# SID-Monitor.net
KiCad netlist of a schematic drawn in EAGLE
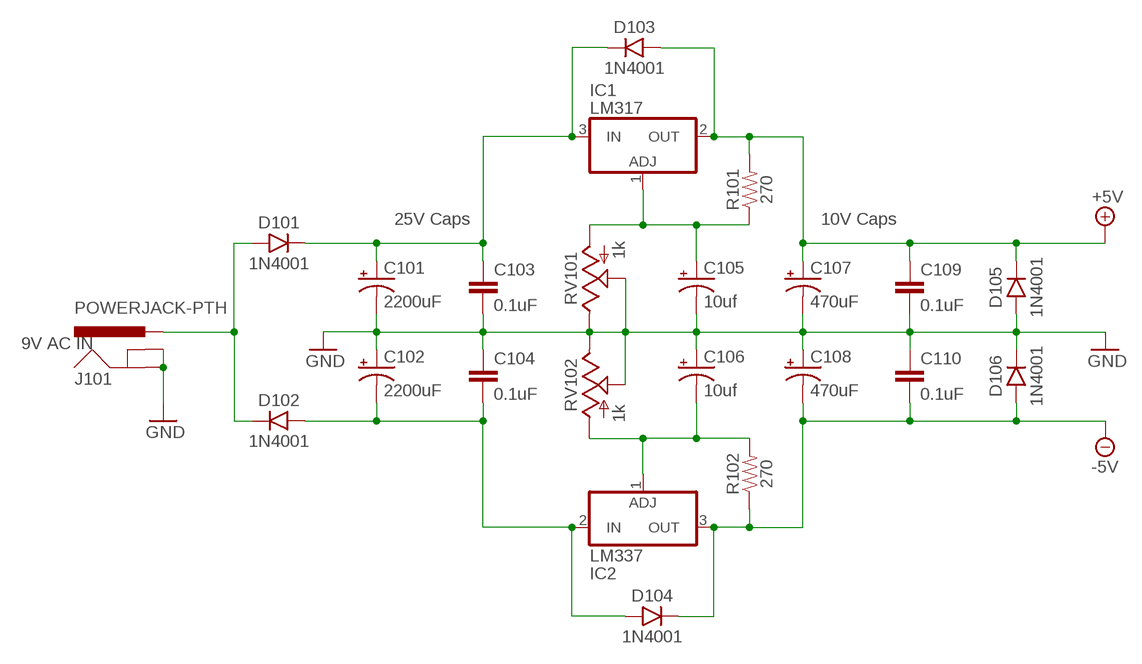
[diagram p0: schematic, sheet 1]
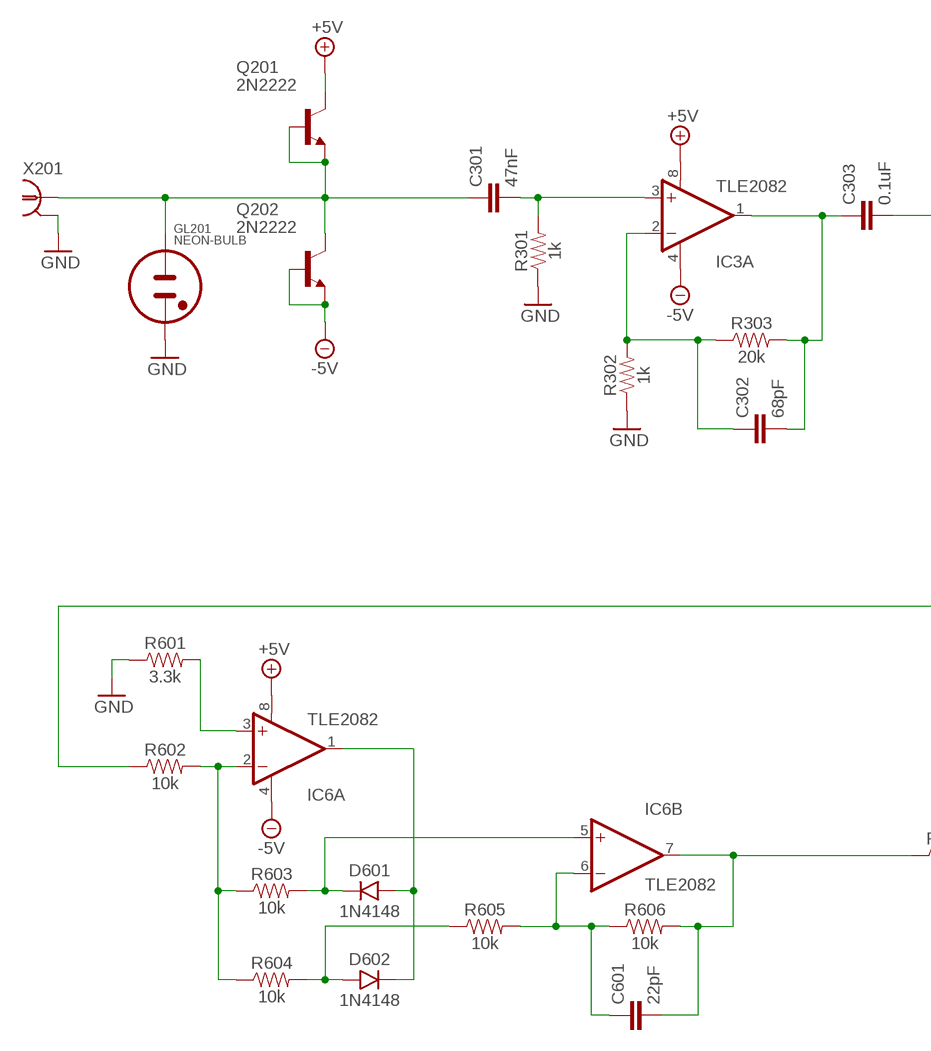
[diagram p1: schematic, sheet 2, part 1 of 2]
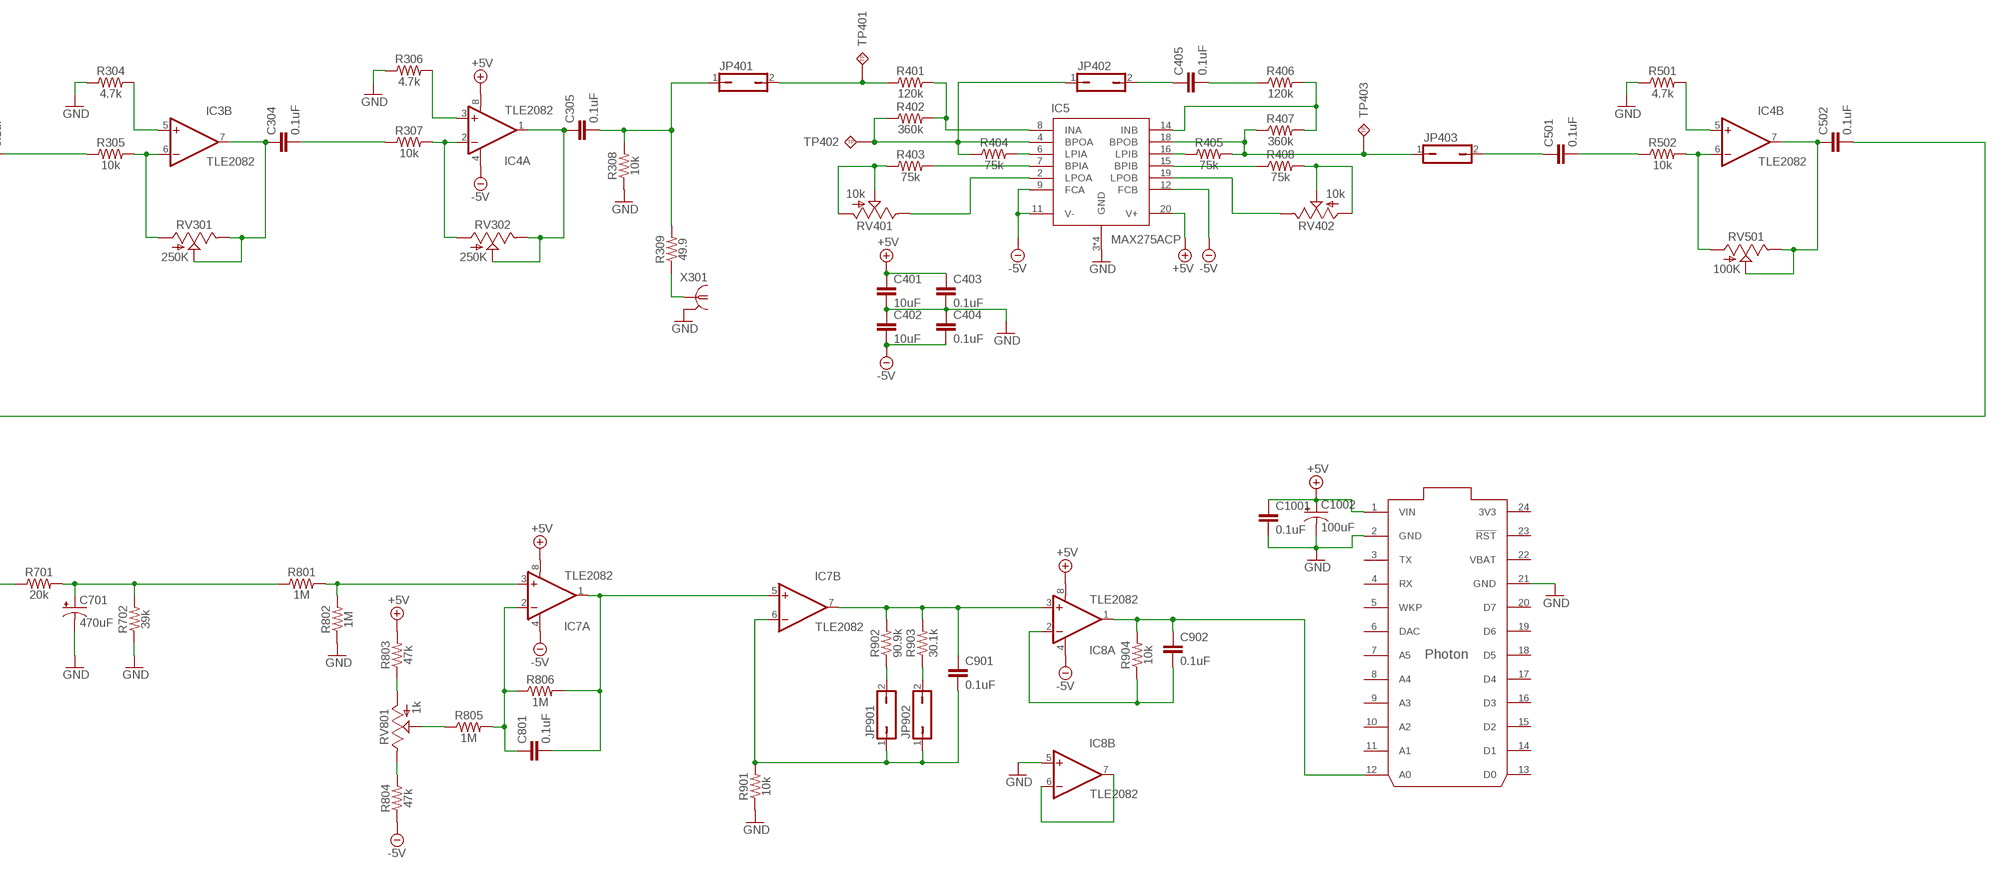
[diagram p2: schematic, sheet 2, part 2 of 2]

(export (version "E")
  (design (tool "Eeschema 10.0.6"))
  (components
    (comp (ref "C301")
      (value "47nF")
      (footprint "eagle-import:CAPACITOR-2.5MM")
      (libsource (lib "eagle-import") (part "CAPACITOR-2.5MM"))
    )
    (comp (ref "C302")
      (value "68pF")
      (footprint "eagle-import:CAPACITOR-2.5MM")
      (libsource (lib "eagle-import") (part "CAPACITOR-2.5MM"))
    )
    (comp (ref "C303")
      (value "0.1uF")
      (footprint "eagle-import:CAPACITOR-2.5MM")
      (libsource (lib "eagle-import") (part "CAPACITOR-2.5MM"))
    )
    (comp (ref "C304")
      (value "0.1uF")
      (footprint "eagle-import:CAPACITOR-2.5MM")
      (libsource (lib "eagle-import") (part "CAPACITOR-2.5MM"))
    )
    (comp (ref "C305")
      (value "0.1uF")
      (footprint "eagle-import:CAPACITOR-2.5MM")
      (libsource (lib "eagle-import") (part "CAPACITOR-2.5MM"))
    )
    (comp (ref "C401")
      (value "10uF")
      (footprint "eagle-import:CAPACITOR-5MM")
      (libsource (lib "eagle-import") (part "CAPACITOR-5MM"))
    )
    (comp (ref "C402")
      (value "10uF")
      (footprint "eagle-import:CAPACITOR-5MM")
      (libsource (lib "eagle-import") (part "CAPACITOR-5MM"))
    )
    (comp (ref "C403")
      (value "0.1uF")
      (footprint "eagle-import:CAPACITOR-2.5MM")
      (libsource (lib "eagle-import") (part "CAPACITOR-2.5MM"))
    )
    (comp (ref "C404")
      (value "0.1uF")
      (footprint "eagle-import:CAPACITOR-2.5MM")
      (libsource (lib "eagle-import") (part "CAPACITOR-2.5MM"))
    )
    (comp (ref "C405")
      (value "0.1uF")
      (footprint "eagle-import:CAPACITOR-2.5MM")
      (libsource (lib "eagle-import") (part "CAPACITOR-2.5MM"))
    )
    (comp (ref "C501")
      (value "0.1uF")
      (footprint "eagle-import:CAPACITOR-2.5MM")
      (libsource (lib "eagle-import") (part "CAPACITOR-2.5MM"))
    )
    (comp (ref "C502")
      (value "0.1uF")
      (footprint "eagle-import:CAPACITOR-2.5MM")
      (libsource (lib "eagle-import") (part "CAPACITOR-2.5MM"))
    )
    (comp (ref "C601")
      (value "22pF")
      (footprint "eagle-import:CAPACITOR-2.5MM")
      (libsource (lib "eagle-import") (part "CAPACITOR-2.5MM"))
    )
    (comp (ref "C701")
      (value "470uF")
      (footprint "eagle-import:CAP-POL-3.5-8")
      (libsource (lib "eagle-import") (part "CAPACITOR-POLARIZED-3.5-8"))
    )
    (comp (ref "C801")
      (value "0.1uF")
      (footprint "eagle-import:CAPACITOR-2.5MM")
      (libsource (lib "eagle-import") (part "CAPACITOR-2.5MM"))
    )
    (comp (ref "C901")
      (value "0.1uF")
      (footprint "eagle-import:CAPACITOR-2.5MM")
      (libsource (lib "eagle-import") (part "CAPACITOR-2.5MM"))
    )
    (comp (ref "C902")
      (value "0.1uF")
      (footprint "eagle-import:CAPACITOR-2.5MM")
      (libsource (lib "eagle-import") (part "CAPACITOR-2.5MM"))
    )
    (comp (ref "C1001")
      (value "0.1uF")
      (footprint "eagle-import:CAPACITOR-2.5MM")
      (libsource (lib "eagle-import") (part "CAPACITOR-2.5MM"))
    )
    (comp (ref "C1002")
      (value "100uF")
      (footprint "eagle-import:CAP-POL-3.5-8")
      (libsource (lib "eagle-import") (part "CAPACITOR-POLARIZED-3.5-8"))
    )
    (comp (ref "D601")
      (value "1N4148")
      (footprint "eagle-import:DIODE-DO-35")
      (libsource (lib "eagle-import") (part "DIODE-1N4148"))
    )
    (comp (ref "D602")
      (value "1N4148")
      (footprint "eagle-import:DIODE-DO-35")
      (libsource (lib "eagle-import") (part "DIODE-1N4148"))
    )
    (comp (ref "GL201")
      (value "NEON-BULB")
      (footprint "eagle-import:NEON-BULB")
      (libsource (lib "eagle-import") (part "NEON-BULB"))
    )
    (comp (ref "IC3")
      (value "TLE2082")
      (footprint "eagle-import:DIP08")
      (libsource (lib "eagle-import") (part "TLE2082"))
    )
    (comp (ref "IC4")
      (value "TLE2082")
      (footprint "eagle-import:DIP08")
      (libsource (lib "eagle-import") (part "TLE2082"))
    )
    (comp (ref "IC5")
      (value "MAX275ACP")
      (footprint "eagle-import:DIP20")
      (libsource (lib "eagle-import") (part "MAX275ACP"))
    )
    (comp (ref "IC6")
      (value "TLE2082")
      (footprint "eagle-import:DIP08")
      (libsource (lib "eagle-import") (part "TLE2082"))
    )
    (comp (ref "IC7")
      (value "TLE2082")
      (footprint "eagle-import:DIP08")
      (libsource (lib "eagle-import") (part "TLE2082"))
    )
    (comp (ref "IC8")
      (value "TLE2082")
      (footprint "eagle-import:DIP08")
      (libsource (lib "eagle-import") (part "TLE2082"))
    )
    (comp (ref "IC9")
      (value "PHOTON")
      (footprint "eagle-import:PHOTON")
      (libsource (lib "eagle-import") (part "PHOTON_WITH_HEADERS"))
    )
    (comp (ref "JP401")
      (value "JUMPER1")
      (footprint "eagle-import:JUMPER1")
      (libsource (lib "eagle-import") (part "JUMPER1"))
    )
    (comp (ref "JP402")
      (value "JUMPER1")
      (footprint "eagle-import:JUMPER1")
      (libsource (lib "eagle-import") (part "JUMPER1"))
    )
    (comp (ref "JP403")
      (value "JUMPER1")
      (footprint "eagle-import:JUMPER1")
      (libsource (lib "eagle-import") (part "JUMPER1"))
    )
    (comp (ref "JP901")
      (value "JUMPER1")
      (footprint "eagle-import:JUMPER1")
      (libsource (lib "eagle-import") (part "JUMPER1"))
    )
    (comp (ref "JP902")
      (value "JUMPER1")
      (footprint "eagle-import:JUMPER1")
      (libsource (lib "eagle-import") (part "JUMPER1"))
    )
    (comp (ref "Q201")
      (value "2N2222")
      (footprint "eagle-import:TO92-INLINE")
      (libsource (lib "eagle-import") (part "2N2222"))
    )
    (comp (ref "Q202")
      (value "2N2222")
      (footprint "eagle-import:TO92-INLINE")
      (libsource (lib "eagle-import") (part "2N2222"))
    )
    (comp (ref "R301")
      (value "1k")
      (footprint "eagle-import:AXIAL-7.5MM")
      (libsource (lib "eagle-import") (part "RESISTOR-7.5MM"))
    )
    (comp (ref "R302")
      (value "1k")
      (footprint "eagle-import:AXIAL-7.5MM")
      (libsource (lib "eagle-import") (part "RESISTOR-7.5MM"))
    )
    (comp (ref "R303")
      (value "20k")
      (footprint "eagle-import:AXIAL-7.5MM")
      (libsource (lib "eagle-import") (part "RESISTOR-7.5MM"))
    )
    (comp (ref "R304")
      (value "4.7k")
      (footprint "eagle-import:AXIAL-7.5MM")
      (libsource (lib "eagle-import") (part "RESISTOR-7.5MM"))
    )
    (comp (ref "R305")
      (value "10k")
      (footprint "eagle-import:AXIAL-7.5MM")
      (libsource (lib "eagle-import") (part "RESISTOR-7.5MM"))
    )
    (comp (ref "R306")
      (value "4.7k")
      (footprint "eagle-import:AXIAL-7.5MM")
      (libsource (lib "eagle-import") (part "RESISTOR-7.5MM"))
    )
    (comp (ref "R307")
      (value "10k")
      (footprint "eagle-import:AXIAL-7.5MM")
      (libsource (lib "eagle-import") (part "RESISTOR-7.5MM"))
    )
    (comp (ref "R308")
      (value "10k")
      (footprint "eagle-import:AXIAL-7.5MM")
      (libsource (lib "eagle-import") (part "RESISTOR-7.5MM"))
    )
    (comp (ref "R309")
      (value "49.9")
      (footprint "eagle-import:AXIAL-7.5MM")
      (libsource (lib "eagle-import") (part "RESISTOR-7.5MM"))
    )
    (comp (ref "R401")
      (value "120k")
      (footprint "eagle-import:AXIAL-7.5MM")
      (libsource (lib "eagle-import") (part "RESISTOR-7.5MM"))
    )
    (comp (ref "R402")
      (value "360k")
      (footprint "eagle-import:AXIAL-7.5MM")
      (libsource (lib "eagle-import") (part "RESISTOR-7.5MM"))
    )
    (comp (ref "R403")
      (value "75k")
      (footprint "eagle-import:AXIAL-7.5MM")
      (libsource (lib "eagle-import") (part "RESISTOR-7.5MM"))
    )
    (comp (ref "R404")
      (value "75k")
      (footprint "eagle-import:AXIAL-7.5MM")
      (libsource (lib "eagle-import") (part "RESISTOR-7.5MM"))
    )
    (comp (ref "R405")
      (value "75k")
      (footprint "eagle-import:AXIAL-7.5MM")
      (libsource (lib "eagle-import") (part "RESISTOR-7.5MM"))
    )
    (comp (ref "R406")
      (value "120k")
      (footprint "eagle-import:AXIAL-7.5MM")
      (libsource (lib "eagle-import") (part "RESISTOR-7.5MM"))
    )
    (comp (ref "R407")
      (value "360k")
      (footprint "eagle-import:AXIAL-7.5MM")
      (libsource (lib "eagle-import") (part "RESISTOR-7.5MM"))
    )
    (comp (ref "R408")
      (value "75k")
      (footprint "eagle-import:AXIAL-7.5MM")
      (libsource (lib "eagle-import") (part "RESISTOR-7.5MM"))
    )
    (comp (ref "R501")
      (value "4.7k")
      (footprint "eagle-import:AXIAL-7.5MM")
      (libsource (lib "eagle-import") (part "RESISTOR-7.5MM"))
    )
    (comp (ref "R502")
      (value "10k")
      (footprint "eagle-import:AXIAL-7.5MM")
      (libsource (lib "eagle-import") (part "RESISTOR-7.5MM"))
    )
    (comp (ref "R601")
      (value "3.3k")
      (footprint "eagle-import:AXIAL-7.5MM")
      (libsource (lib "eagle-import") (part "RESISTOR-7.5MM"))
    )
    (comp (ref "R602")
      (value "10k")
      (footprint "eagle-import:AXIAL-7.5MM")
      (libsource (lib "eagle-import") (part "RESISTOR-7.5MM"))
    )
    (comp (ref "R603")
      (value "10k")
      (footprint "eagle-import:AXIAL-7.5MM")
      (libsource (lib "eagle-import") (part "RESISTOR-7.5MM"))
    )
    (comp (ref "R604")
      (value "10k")
      (footprint "eagle-import:AXIAL-7.5MM")
      (libsource (lib "eagle-import") (part "RESISTOR-7.5MM"))
    )
    (comp (ref "R605")
      (value "10k")
      (footprint "eagle-import:AXIAL-7.5MM")
      (libsource (lib "eagle-import") (part "RESISTOR-7.5MM"))
    )
    (comp (ref "R606")
      (value "10k")
      (footprint "eagle-import:AXIAL-7.5MM")
      (libsource (lib "eagle-import") (part "RESISTOR-7.5MM"))
    )
    (comp (ref "R701")
      (value "20k")
      (footprint "eagle-import:AXIAL-7.5MM")
      (libsource (lib "eagle-import") (part "RESISTOR-7.5MM"))
    )
    (comp (ref "R702")
      (value "39k")
      (footprint "eagle-import:AXIAL-7.5MM")
      (libsource (lib "eagle-import") (part "RESISTOR-7.5MM"))
    )
    (comp (ref "R801")
      (value "1M")
      (footprint "eagle-import:AXIAL-7.5MM")
      (libsource (lib "eagle-import") (part "RESISTOR-7.5MM"))
    )
    (comp (ref "R802")
      (value "1M")
      (footprint "eagle-import:AXIAL-7.5MM")
      (libsource (lib "eagle-import") (part "RESISTOR-7.5MM"))
    )
    (comp (ref "R803")
      (value "47k")
      (footprint "eagle-import:AXIAL-7.5MM")
      (libsource (lib "eagle-import") (part "RESISTOR-7.5MM"))
    )
    (comp (ref "R804")
      (value "47k")
      (footprint "eagle-import:AXIAL-7.5MM")
      (libsource (lib "eagle-import") (part "RESISTOR-7.5MM"))
    )
    (comp (ref "R805")
      (value "1M")
      (footprint "eagle-import:AXIAL-7.5MM")
      (libsource (lib "eagle-import") (part "RESISTOR-7.5MM"))
    )
    (comp (ref "R806")
      (value "1M")
      (footprint "eagle-import:AXIAL-7.5MM")
      (libsource (lib "eagle-import") (part "RESISTOR-7.5MM"))
    )
    (comp (ref "R901")
      (value "10k")
      (footprint "eagle-import:AXIAL-7.5MM")
      (libsource (lib "eagle-import") (part "RESISTOR-7.5MM"))
    )
    (comp (ref "R902")
      (value "90.9k")
      (footprint "eagle-import:AXIAL-7.5MM")
      (libsource (lib "eagle-import") (part "RESISTOR-7.5MM"))
    )
    (comp (ref "R903")
      (value "30.1k")
      (footprint "eagle-import:AXIAL-7.5MM")
      (libsource (lib "eagle-import") (part "RESISTOR-7.5MM"))
    )
    (comp (ref "R904")
      (value "10k")
      (footprint "eagle-import:AXIAL-7.5MM")
      (libsource (lib "eagle-import") (part "RESISTOR-7.5MM"))
    )
    (comp (ref "RV301")
      (value "250K")
      (footprint "eagle-import:TRIM_POT")
      (libsource (lib "eagle-import") (part "POTTRIM"))
    )
    (comp (ref "RV302")
      (value "250K")
      (footprint "eagle-import:TRIM_POT")
      (libsource (lib "eagle-import") (part "POTTRIM"))
    )
    (comp (ref "RV401")
      (value "10k")
      (footprint "eagle-import:TRIM_POT")
      (libsource (lib "eagle-import") (part "POTTRIM"))
    )
    (comp (ref "RV402")
      (value "10k")
      (footprint "eagle-import:TRIM_POT")
      (libsource (lib "eagle-import") (part "POTTRIM"))
    )
    (comp (ref "RV501")
      (value "100K")
      (footprint "eagle-import:TRIM_POT")
      (libsource (lib "eagle-import") (part "POTTRIM"))
    )
    (comp (ref "RV801")
      (value "1k")
      (footprint "eagle-import:TRIM_POT")
      (libsource (lib "eagle-import") (part "POTTRIM"))
    )
    (comp (ref "TP401")
      (value "TESTPOINT-TH")
      (footprint "eagle-import:1X01")
      (libsource (lib "eagle-import") (part "TESTPOINT-TH"))
    )
    (comp (ref "TP402")
      (value "TESTPOINT-TH")
      (footprint "eagle-import:1X01")
      (libsource (lib "eagle-import") (part "TESTPOINT-TH"))
    )
    (comp (ref "TP403")
      (value "TESTPOINT-TH")
      (footprint "eagle-import:1X01")
      (libsource (lib "eagle-import") (part "TESTPOINT-TH"))
    )
    (comp (ref "X201")
      (value "5414373")
      (footprint "eagle-import:5414373")
      (libsource (lib "eagle-import") (part "5414373"))
    )
    (comp (ref "X301")
      (value "5414373")
      (footprint "eagle-import:5414373")
      (libsource (lib "eagle-import") (part "5414373"))
    )
    (comp (ref "C101")
      (value "2200uF")
      (footprint "eagle-import:CAP-POL-5-13")
      (libsource (lib "eagle-import") (part "CAPACITOR-POLARIZED-5-13"))
    )
    (comp (ref "C102")
      (value "2200uF")
      (footprint "eagle-import:CAP-POL-5-13")
      (libsource (lib "eagle-import") (part "CAPACITOR-POLARIZED-5-13"))
    )
    (comp (ref "C103")
      (value "0.1uF")
      (footprint "eagle-import:CAPACITOR-2.5MM")
      (libsource (lib "eagle-import") (part "CAPACITOR-2.5MM"))
    )
    (comp (ref "C104")
      (value "0.1uF")
      (footprint "eagle-import:CAPACITOR-2.5MM")
      (libsource (lib "eagle-import") (part "CAPACITOR-2.5MM"))
    )
    (comp (ref "C105")
      (value "10uf")
      (footprint "eagle-import:CAP-POL-2.5-5")
      (libsource (lib "eagle-import") (part "CAPACITOR-POLARIZED-2.5-5"))
    )
    (comp (ref "C106")
      (value "10uf")
      (footprint "eagle-import:CAP-POL-2.5-5")
      (libsource (lib "eagle-import") (part "CAPACITOR-POLARIZED-2.5-5"))
    )
    (comp (ref "C107")
      (value "470uF")
      (footprint "eagle-import:CAP-POL-3.5-8")
      (libsource (lib "eagle-import") (part "CAPACITOR-POLARIZED-3.5-8"))
    )
    (comp (ref "C108")
      (value "470uF")
      (footprint "eagle-import:CAP-POL-3.5-8")
      (libsource (lib "eagle-import") (part "CAPACITOR-POLARIZED-3.5-8"))
    )
    (comp (ref "C109")
      (value "0.1uF")
      (footprint "eagle-import:CAPACITOR-2.5MM")
      (libsource (lib "eagle-import") (part "CAPACITOR-2.5MM"))
    )
    (comp (ref "C110")
      (value "0.1uF")
      (footprint "eagle-import:CAPACITOR-2.5MM")
      (libsource (lib "eagle-import") (part "CAPACITOR-2.5MM"))
    )
    (comp (ref "D101")
      (value "1N4001")
      (footprint "eagle-import:DO-41")
      (libsource (lib "eagle-import") (part "DIODE-1N4001"))
    )
    (comp (ref "D102")
      (value "1N4001")
      (footprint "eagle-import:DO-41")
      (libsource (lib "eagle-import") (part "DIODE-1N4001"))
    )
    (comp (ref "D103")
      (value "1N4001")
      (footprint "eagle-import:DO-41")
      (libsource (lib "eagle-import") (part "DIODE-1N4001"))
    )
    (comp (ref "D104")
      (value "1N4001")
      (footprint "eagle-import:DO-41")
      (libsource (lib "eagle-import") (part "DIODE-1N4001"))
    )
    (comp (ref "D105")
      (value "1N4001")
      (footprint "eagle-import:DO-41")
      (libsource (lib "eagle-import") (part "DIODE-1N4001"))
    )
    (comp (ref "D106")
      (value "1N4001")
      (footprint "eagle-import:DO-41")
      (libsource (lib "eagle-import") (part "DIODE-1N4001"))
    )
    (comp (ref "IC1")
      (value "LM317")
      (footprint "eagle-import:TO220BV")
      (libsource (lib "eagle-import") (part "LM317"))
    )
    (comp (ref "IC2")
      (value "LM337")
      (footprint "eagle-import:TO220BV")
      (libsource (lib "eagle-import") (part "LM337"))
    )
    (comp (ref "J101")
      (value "POWERJACK-PTH")
      (footprint "eagle-import:POWER_JACK_PTH")
      (libsource (lib "eagle-import") (part "POWERJACK-PTH"))
    )
    (comp (ref "R101")
      (value "270")
      (footprint "eagle-import:AXIAL-7.5MM")
      (libsource (lib "eagle-import") (part "RESISTOR-7.5MM"))
    )
    (comp (ref "R102")
      (value "270")
      (footprint "eagle-import:AXIAL-7.5MM")
      (libsource (lib "eagle-import") (part "RESISTOR-7.5MM"))
    )
    (comp (ref "RV101")
      (value "1k")
      (footprint "eagle-import:TRIM_POT")
      (libsource (lib "eagle-import") (part "POTTRIM"))
    )
    (comp (ref "RV102")
      (value "1k")
      (footprint "eagle-import:TRIM_POT")
      (libsource (lib "eagle-import") (part "POTTRIM"))
    )
  )
  (nets
    (net (code "1") (name "+5V") (class "Default")
      (node (ref "C1001") (pin "1") (pinfunction "1_1") (pintype "passive"))
      (node (ref "C1002") (pin "+") (pinfunction "+_+") (pintype "passive"))
      (node (ref "C107") (pin "+") (pinfunction "+_+") (pintype "passive"))
      (node (ref "C109") (pin "1") (pinfunction "1_1") (pintype "passive"))
      (node (ref "C401") (pin "1") (pinfunction "1_1") (pintype "passive"))
      (node (ref "C403") (pin "1") (pinfunction "1_1") (pintype "passive"))
      (node (ref "D103") (pin "1") (pinfunction "+_1") (pintype "passive"))
      (node (ref "D105") (pin "2") (pinfunction "-_2") (pintype "passive"))
      (node (ref "IC1") (pin "2") (pinfunction "OUT_2") (pintype "passive"))
      (node (ref "IC3") (pin "8") (pinfunction "V+_8") (pintype "power_in"))
      (node (ref "IC4") (pin "8") (pinfunction "V+_8") (pintype "power_in"))
      (node (ref "IC5") (pin "20") (pinfunction "V+_20") (pintype "power_in"))
      (node (ref "IC6") (pin "8") (pinfunction "V+_8") (pintype "power_in"))
      (node (ref "IC7") (pin "8") (pinfunction "V+_8") (pintype "power_in"))
      (node (ref "IC8") (pin "8") (pinfunction "V+_8") (pintype "power_in"))
      (node (ref "IC9") (pin "1") (pinfunction "VIN_1") (pintype "power_in"))
      (node (ref "Q201") (pin "3") (pinfunction "C_3") (pintype "passive"))
      (node (ref "R101") (pin "P$2") (pinfunction "2_P$2") (pintype "passive"))
      (node (ref "R803") (pin "P$2") (pinfunction "2_P$2") (pintype "passive"))
    )
    (net (code "2") (name "-5V") (class "Default")
      (node (ref "C108") (pin "-") (pinfunction "-_-") (pintype "passive"))
      (node (ref "C110") (pin "2") (pinfunction "2_2") (pintype "passive"))
      (node (ref "C402") (pin "2") (pinfunction "2_2") (pintype "passive"))
      (node (ref "C404") (pin "2") (pinfunction "2_2") (pintype "passive"))
      (node (ref "D104") (pin "2") (pinfunction "-_2") (pintype "passive"))
      (node (ref "D106") (pin "1") (pinfunction "+_1") (pintype "passive"))
      (node (ref "IC2") (pin "3") (pinfunction "OUT_3") (pintype "passive"))
      (node (ref "IC3") (pin "4") (pinfunction "V-_4") (pintype "power_in"))
      (node (ref "IC4") (pin "4") (pinfunction "V-_4") (pintype "power_in"))
      (node (ref "IC5") (pin "11") (pinfunction "V-_11") (pintype "power_in"))
      (node (ref "IC5") (pin "12") (pinfunction "FCB_12") (pintype "bidirectional"))
      (node (ref "IC5") (pin "9") (pinfunction "FCA_9") (pintype "bidirectional"))
      (node (ref "IC6") (pin "4") (pinfunction "V-_4") (pintype "power_in"))
      (node (ref "IC7") (pin "4") (pinfunction "V-_4") (pintype "power_in"))
      (node (ref "IC8") (pin "4") (pinfunction "V-_4") (pintype "power_in"))
      (node (ref "Q202") (pin "1") (pinfunction "E_1") (pintype "passive"))
      (node (ref "Q202") (pin "2") (pinfunction "B_2") (pintype "passive"))
      (node (ref "R102") (pin "P$1") (pinfunction "1_P$1") (pintype "passive"))
      (node (ref "R804") (pin "P$1") (pinfunction "1_P$1") (pintype "passive"))
    )
    (net (code "3") (name "3V3") (class "Default")
      (node (ref "IC9") (pin "24") (pinfunction "3V3_24") (pintype "power_in"))
    )
    (net (code "4") (name "GND") (class "Default")
      (node (ref "C1001") (pin "2") (pinfunction "2_2") (pintype "passive"))
      (node (ref "C1002") (pin "-") (pinfunction "-_-") (pintype "passive"))
      (node (ref "C101") (pin "-") (pinfunction "-_-") (pintype "passive"))
      (node (ref "C102") (pin "+") (pinfunction "+_+") (pintype "passive"))
      (node (ref "C103") (pin "2") (pinfunction "2_2") (pintype "passive"))
      (node (ref "C104") (pin "1") (pinfunction "1_1") (pintype "passive"))
      (node (ref "C105") (pin "-") (pinfunction "-_-") (pintype "passive"))
      (node (ref "C106") (pin "+") (pinfunction "+_+") (pintype "passive"))
      (node (ref "C107") (pin "-") (pinfunction "-_-") (pintype "passive"))
      (node (ref "C108") (pin "+") (pinfunction "+_+") (pintype "passive"))
      (node (ref "C109") (pin "2") (pinfunction "2_2") (pintype "passive"))
      (node (ref "C110") (pin "1") (pinfunction "1_1") (pintype "passive"))
      (node (ref "C401") (pin "2") (pinfunction "2_2") (pintype "passive"))
      (node (ref "C402") (pin "1") (pinfunction "1_1") (pintype "passive"))
      (node (ref "C403") (pin "2") (pinfunction "2_2") (pintype "passive"))
      (node (ref "C404") (pin "1") (pinfunction "1_1") (pintype "passive"))
      (node (ref "C701") (pin "-") (pinfunction "-_-") (pintype "passive"))
      (node (ref "D105") (pin "1") (pinfunction "+_1") (pintype "passive"))
      (node (ref "D106") (pin "2") (pinfunction "-_2") (pintype "passive"))
      (node (ref "GL201") (pin "2") (pinfunction "C_2") (pintype "passive"))
      (node (ref "IC5") (pin "10") (pinfunction "GND_10") (pintype "power_in"))
      (node (ref "IC5") (pin "17") (pinfunction "GND_17") (pintype "power_in"))
      (node (ref "IC5") (pin "3") (pinfunction "GND_3") (pintype "power_in"))
      (node (ref "IC5") (pin "5") (pinfunction "GND_5") (pintype "power_in"))
      (node (ref "IC8") (pin "5") (pinfunction "+IN_5") (pintype "input"))
      (node (ref "IC9") (pin "2") (pinfunction "GND_2") (pintype "power_in"))
      (node (ref "IC9") (pin "21") (pinfunction "GND_21") (pintype "power_in"))
      (node (ref "J101") (pin "GND") (pinfunction "GND_GND") (pintype "bidirectional"))
      (node (ref "J101") (pin "GNDBREAK") (pinfunction "GNDBREAK_GNDBREAK") (pintype "bidirectional"))
      (node (ref "R301") (pin "P$1") (pinfunction "1_P$1") (pintype "passive"))
      (node (ref "R302") (pin "P$1") (pinfunction "1_P$1") (pintype "passive"))
      (node (ref "R304") (pin "P$1") (pinfunction "1_P$1") (pintype "passive"))
      (node (ref "R306") (pin "P$1") (pinfunction "1_P$1") (pintype "passive"))
      (node (ref "R308") (pin "P$1") (pinfunction "1_P$1") (pintype "passive"))
      (node (ref "R501") (pin "P$1") (pinfunction "1_P$1") (pintype "passive"))
      (node (ref "R601") (pin "P$1") (pinfunction "1_P$1") (pintype "passive"))
      (node (ref "R702") (pin "P$1") (pinfunction "1_P$1") (pintype "passive"))
      (node (ref "R802") (pin "P$1") (pinfunction "1_P$1") (pintype "passive"))
      (node (ref "R901") (pin "P$1") (pinfunction "1_P$1") (pintype "passive"))
      (node (ref "RV101") (pin "1") (pinfunction "S_1") (pintype "passive"))
      (node (ref "RV101") (pin "2") (pinfunction "E_2") (pintype "passive"))
      (node (ref "RV102") (pin "1") (pinfunction "S_1") (pintype "passive"))
      (node (ref "RV102") (pin "2") (pinfunction "E_2") (pintype "passive"))
      (node (ref "X201") (pin "1") (pinfunction "2_1") (pintype "passive"))
      (node (ref "X201") (pin "2") (pinfunction "2_2") (pintype "passive"))
      (node (ref "X301") (pin "1") (pinfunction "2_1") (pintype "passive"))
      (node (ref "X301") (pin "2") (pinfunction "2_2") (pintype "passive"))
    )
    (net (code "5") (name "Net-(C405-Pad1)") (class "Default")
      (node (ref "C405") (pin "1") (pinfunction "1_1") (pintype "passive"))
      (node (ref "JP402") (pin "2") (pinfunction "2_2") (pintype "passive"))
    )
    (net (code "6") (name "Net-(C501-Pad1)") (class "Default")
      (node (ref "C501") (pin "1") (pinfunction "1_1") (pintype "passive"))
      (node (ref "JP403") (pin "2") (pinfunction "2_2") (pintype "passive"))
    )
    (net (code "7") (name "Net-(D101-+)") (class "Default")
      (node (ref "D101") (pin "1") (pinfunction "+_1") (pintype "passive"))
      (node (ref "D102") (pin "2") (pinfunction "-_2") (pintype "passive"))
      (node (ref "J101") (pin "PWR") (pinfunction "PWR_PWR") (pintype "bidirectional"))
    )
    (net (code "8") (name "Net-(D101--)") (class "Default")
      (node (ref "C101") (pin "+") (pinfunction "+_+") (pintype "passive"))
      (node (ref "C103") (pin "1") (pinfunction "1_1") (pintype "passive"))
      (node (ref "D101") (pin "2") (pinfunction "-_2") (pintype "passive"))
      (node (ref "D103") (pin "2") (pinfunction "-_2") (pintype "passive"))
      (node (ref "IC1") (pin "3") (pinfunction "IN_3") (pintype "input"))
    )
    (net (code "9") (name "Net-(D102-+)") (class "Default")
      (node (ref "C102") (pin "-") (pinfunction "-_-") (pintype "passive"))
      (node (ref "C104") (pin "2") (pinfunction "2_2") (pintype "passive"))
      (node (ref "D102") (pin "1") (pinfunction "+_1") (pintype "passive"))
      (node (ref "D104") (pin "1") (pinfunction "+_1") (pintype "passive"))
      (node (ref "IC2") (pin "2") (pinfunction "IN_2") (pintype "input"))
    )
    (net (code "10") (name "Net-(D601-+)") (class "Default")
      (node (ref "D601") (pin "A") (pinfunction "+_A") (pintype "passive"))
      (node (ref "D602") (pin "C") (pinfunction "-_C") (pintype "passive"))
      (node (ref "IC6") (pin "1") (pinfunction "OUT_1") (pintype "output"))
    )
    (net (code "11") (name "Net-(D601--)") (class "Default")
      (node (ref "D601") (pin "C") (pinfunction "-_C") (pintype "passive"))
      (node (ref "IC6") (pin "5") (pinfunction "+IN_5") (pintype "input"))
      (node (ref "R603") (pin "P$2") (pinfunction "2_P$2") (pintype "passive"))
    )
    (net (code "12") (name "Net-(D602-+)") (class "Default")
      (node (ref "D602") (pin "A") (pinfunction "+_A") (pintype "passive"))
      (node (ref "R604") (pin "P$2") (pinfunction "2_P$2") (pintype "passive"))
      (node (ref "R605") (pin "P$1") (pinfunction "1_P$1") (pintype "passive"))
    )
    (net (code "13") (name "Net-(GL201-A)") (class "Default")
      (node (ref "C301") (pin "1") (pinfunction "1_1") (pintype "passive"))
      (node (ref "GL201") (pin "1") (pinfunction "A_1") (pintype "passive"))
      (node (ref "Q201") (pin "1") (pinfunction "E_1") (pintype "passive"))
      (node (ref "Q201") (pin "2") (pinfunction "B_2") (pintype "passive"))
      (node (ref "Q202") (pin "3") (pinfunction "C_3") (pintype "passive"))
      (node (ref "X201") (pin "3") (pinfunction "1_3") (pintype "passive"))
    )
    (net (code "14") (name "Net-(IC1-ADJ)") (class "Default")
      (node (ref "C105") (pin "+") (pinfunction "+_+") (pintype "passive"))
      (node (ref "IC1") (pin "1") (pinfunction "ADJ_1") (pintype "passive"))
      (node (ref "R101") (pin "P$1") (pinfunction "1_P$1") (pintype "passive"))
      (node (ref "RV101") (pin "3") (pinfunction "A_3") (pintype "passive"))
    )
    (net (code "15") (name "Net-(IC2-ADJ)") (class "Default")
      (node (ref "C106") (pin "-") (pinfunction "-_-") (pintype "passive"))
      (node (ref "IC2") (pin "1") (pinfunction "ADJ_1") (pintype "passive"))
      (node (ref "R102") (pin "P$2") (pinfunction "2_P$2") (pintype "passive"))
      (node (ref "RV102") (pin "3") (pinfunction "A_3") (pintype "passive"))
    )
    (net (code "16") (name "Net-(IC3A-+IN)") (class "Default")
      (node (ref "C301") (pin "2") (pinfunction "2_2") (pintype "passive"))
      (node (ref "IC3") (pin "3") (pinfunction "+IN_3") (pintype "input"))
      (node (ref "R301") (pin "P$2") (pinfunction "2_P$2") (pintype "passive"))
    )
    (net (code "17") (name "Net-(IC3A--IN)") (class "Default")
      (node (ref "C302") (pin "1") (pinfunction "1_1") (pintype "passive"))
      (node (ref "IC3") (pin "2") (pinfunction "-IN_2") (pintype "input"))
      (node (ref "R302") (pin "P$2") (pinfunction "2_P$2") (pintype "passive"))
      (node (ref "R303") (pin "P$1") (pinfunction "1_P$1") (pintype "passive"))
    )
    (net (code "18") (name "Net-(IC3A-OUT)") (class "Default")
      (node (ref "C302") (pin "2") (pinfunction "2_2") (pintype "passive"))
      (node (ref "C303") (pin "1") (pinfunction "1_1") (pintype "passive"))
      (node (ref "IC3") (pin "1") (pinfunction "OUT_1") (pintype "output"))
      (node (ref "R303") (pin "P$2") (pinfunction "2_P$2") (pintype "passive"))
    )
    (net (code "19") (name "Net-(IC3B-+IN)") (class "Default")
      (node (ref "IC3") (pin "5") (pinfunction "+IN_5") (pintype "input"))
      (node (ref "R304") (pin "P$2") (pinfunction "2_P$2") (pintype "passive"))
    )
    (net (code "20") (name "Net-(IC3B--IN)") (class "Default")
      (node (ref "IC3") (pin "6") (pinfunction "-IN_6") (pintype "input"))
      (node (ref "R305") (pin "P$2") (pinfunction "2_P$2") (pintype "passive"))
      (node (ref "RV301") (pin "3") (pinfunction "A_3") (pintype "passive"))
    )
    (net (code "21") (name "Net-(IC3B-OUT)") (class "Default")
      (node (ref "C304") (pin "1") (pinfunction "1_1") (pintype "passive"))
      (node (ref "IC3") (pin "7") (pinfunction "OUT_7") (pintype "output"))
      (node (ref "RV301") (pin "1") (pinfunction "S_1") (pintype "passive"))
      (node (ref "RV301") (pin "2") (pinfunction "E_2") (pintype "passive"))
    )
    (net (code "22") (name "Net-(IC4A-+IN)") (class "Default")
      (node (ref "IC4") (pin "3") (pinfunction "+IN_3") (pintype "input"))
      (node (ref "R306") (pin "P$2") (pinfunction "2_P$2") (pintype "passive"))
    )
    (net (code "23") (name "Net-(IC4A--IN)") (class "Default")
      (node (ref "IC4") (pin "2") (pinfunction "-IN_2") (pintype "input"))
      (node (ref "R307") (pin "P$2") (pinfunction "2_P$2") (pintype "passive"))
      (node (ref "RV302") (pin "3") (pinfunction "A_3") (pintype "passive"))
    )
    (net (code "24") (name "Net-(IC4A-OUT)") (class "Default")
      (node (ref "C305") (pin "1") (pinfunction "1_1") (pintype "passive"))
      (node (ref "IC4") (pin "1") (pinfunction "OUT_1") (pintype "output"))
      (node (ref "RV302") (pin "1") (pinfunction "S_1") (pintype "passive"))
      (node (ref "RV302") (pin "2") (pinfunction "E_2") (pintype "passive"))
    )
    (net (code "25") (name "Net-(IC4B-+IN)") (class "Default")
      (node (ref "IC4") (pin "5") (pinfunction "+IN_5") (pintype "input"))
      (node (ref "R501") (pin "P$2") (pinfunction "2_P$2") (pintype "passive"))
    )
    (net (code "26") (name "Net-(IC4B--IN)") (class "Default")
      (node (ref "IC4") (pin "6") (pinfunction "-IN_6") (pintype "input"))
      (node (ref "R502") (pin "P$2") (pinfunction "2_P$2") (pintype "passive"))
      (node (ref "RV501") (pin "3") (pinfunction "A_3") (pintype "passive"))
    )
    (net (code "27") (name "Net-(IC4B-OUT)") (class "Default")
      (node (ref "C502") (pin "1") (pinfunction "1_1") (pintype "passive"))
      (node (ref "IC4") (pin "7") (pinfunction "OUT_7") (pintype "output"))
      (node (ref "RV501") (pin "1") (pinfunction "S_1") (pintype "passive"))
      (node (ref "RV501") (pin "2") (pinfunction "E_2") (pintype "passive"))
    )
    (net (code "28") (name "Net-(IC5-BPIA)") (class "Default")
      (node (ref "IC5") (pin "7") (pinfunction "BPIA_7") (pintype "bidirectional"))
      (node (ref "R403") (pin "P$2") (pinfunction "2_P$2") (pintype "passive"))
    )
    (net (code "29") (name "Net-(IC5-BPIB)") (class "Default")
      (node (ref "IC5") (pin "15") (pinfunction "BPIB_15") (pintype "bidirectional"))
      (node (ref "R408") (pin "P$1") (pinfunction "1_P$1") (pintype "passive"))
    )
    (net (code "30") (name "Net-(IC5-BPOA)") (class "Default")
      (node (ref "IC5") (pin "4") (pinfunction "BPOA_4") (pintype "bidirectional"))
      (node (ref "JP402") (pin "1") (pinfunction "1_1") (pintype "passive"))
      (node (ref "R402") (pin "P$1") (pinfunction "1_P$1") (pintype "passive"))
      (node (ref "R404") (pin "P$1") (pinfunction "1_P$1") (pintype "passive"))
      (node (ref "TP402") (pin "1") (pinfunction "KL_1") (pintype "passive"))
    )
    (net (code "31") (name "Net-(IC5-BPOB)") (class "Default")
      (node (ref "IC5") (pin "18") (pinfunction "BPOB_18") (pintype "bidirectional"))
      (node (ref "JP403") (pin "1") (pinfunction "1_1") (pintype "passive"))
      (node (ref "R405") (pin "P$2") (pinfunction "2_P$2") (pintype "passive"))
      (node (ref "R407") (pin "P$1") (pinfunction "1_P$1") (pintype "passive"))
      (node (ref "TP403") (pin "1") (pinfunction "KL_1") (pintype "passive"))
    )
    (net (code "32") (name "Net-(IC5-INA)") (class "Default")
      (node (ref "IC5") (pin "8") (pinfunction "INA_8") (pintype "bidirectional"))
      (node (ref "R401") (pin "P$2") (pinfunction "2_P$2") (pintype "passive"))
      (node (ref "R402") (pin "P$2") (pinfunction "2_P$2") (pintype "passive"))
    )
    (net (code "33") (name "Net-(IC5-INB)") (class "Default")
      (node (ref "IC5") (pin "14") (pinfunction "INB_14") (pintype "bidirectional"))
      (node (ref "R406") (pin "P$2") (pinfunction "2_P$2") (pintype "passive"))
      (node (ref "R407") (pin "P$2") (pinfunction "2_P$2") (pintype "passive"))
    )
    (net (code "34") (name "Net-(IC5-LPIA)") (class "Default")
      (node (ref "IC5") (pin "6") (pinfunction "LPIA_6") (pintype "bidirectional"))
      (node (ref "R404") (pin "P$2") (pinfunction "2_P$2") (pintype "passive"))
    )
    (net (code "35") (name "Net-(IC5-LPIB)") (class "Default")
      (node (ref "IC5") (pin "16") (pinfunction "LPIB_16") (pintype "bidirectional"))
      (node (ref "R405") (pin "P$1") (pinfunction "1_P$1") (pintype "passive"))
    )
    (net (code "36") (name "Net-(IC5-LPOA)") (class "Default")
      (node (ref "IC5") (pin "2") (pinfunction "LPOA_2") (pintype "bidirectional"))
      (node (ref "RV401") (pin "2") (pinfunction "E_2") (pintype "passive"))
    )
    (net (code "37") (name "Net-(IC5-LPOB)") (class "Default")
      (node (ref "IC5") (pin "19") (pinfunction "LPOB_19") (pintype "bidirectional"))
      (node (ref "RV402") (pin "2") (pinfunction "E_2") (pintype "passive"))
    )
    (net (code "38") (name "Net-(IC6A-+IN)") (class "Default")
      (node (ref "IC6") (pin "3") (pinfunction "+IN_3") (pintype "input"))
      (node (ref "R601") (pin "P$2") (pinfunction "2_P$2") (pintype "passive"))
    )
    (net (code "39") (name "Net-(IC6A--IN)") (class "Default")
      (node (ref "IC6") (pin "2") (pinfunction "-IN_2") (pintype "input"))
      (node (ref "R602") (pin "P$2") (pinfunction "2_P$2") (pintype "passive"))
      (node (ref "R603") (pin "P$1") (pinfunction "1_P$1") (pintype "passive"))
      (node (ref "R604") (pin "P$1") (pinfunction "1_P$1") (pintype "passive"))
    )
    (net (code "40") (name "Net-(IC6B--IN)") (class "Default")
      (node (ref "C601") (pin "1") (pinfunction "1_1") (pintype "passive"))
      (node (ref "IC6") (pin "6") (pinfunction "-IN_6") (pintype "input"))
      (node (ref "R605") (pin "P$2") (pinfunction "2_P$2") (pintype "passive"))
      (node (ref "R606") (pin "P$1") (pinfunction "1_P$1") (pintype "passive"))
    )
    (net (code "41") (name "Net-(IC6B-OUT)") (class "Default")
      (node (ref "C601") (pin "2") (pinfunction "2_2") (pintype "passive"))
      (node (ref "IC6") (pin "7") (pinfunction "OUT_7") (pintype "output"))
      (node (ref "R606") (pin "P$2") (pinfunction "2_P$2") (pintype "passive"))
      (node (ref "R701") (pin "P$1") (pinfunction "1_P$1") (pintype "passive"))
    )
    (net (code "42") (name "Net-(IC7A-+IN)") (class "Default")
      (node (ref "IC7") (pin "3") (pinfunction "+IN_3") (pintype "input"))
      (node (ref "R801") (pin "P$2") (pinfunction "2_P$2") (pintype "passive"))
      (node (ref "R802") (pin "P$2") (pinfunction "2_P$2") (pintype "passive"))
    )
    (net (code "43") (name "Net-(IC7A--IN)") (class "Default")
      (node (ref "C801") (pin "1") (pinfunction "1_1") (pintype "passive"))
      (node (ref "IC7") (pin "2") (pinfunction "-IN_2") (pintype "input"))
      (node (ref "R805") (pin "P$2") (pinfunction "2_P$2") (pintype "passive"))
      (node (ref "R806") (pin "P$1") (pinfunction "1_P$1") (pintype "passive"))
    )
    (net (code "44") (name "Net-(IC7A-OUT)") (class "Default")
      (node (ref "C801") (pin "2") (pinfunction "2_2") (pintype "passive"))
      (node (ref "IC7") (pin "1") (pinfunction "OUT_1") (pintype "output"))
      (node (ref "IC7") (pin "5") (pinfunction "+IN_5") (pintype "input"))
      (node (ref "R806") (pin "P$2") (pinfunction "2_P$2") (pintype "passive"))
    )
    (net (code "45") (name "Net-(IC7B--IN)") (class "Default")
      (node (ref "C901") (pin "2") (pinfunction "2_2") (pintype "passive"))
      (node (ref "IC7") (pin "6") (pinfunction "-IN_6") (pintype "input"))
      (node (ref "JP901") (pin "1") (pinfunction "1_1") (pintype "passive"))
      (node (ref "JP902") (pin "1") (pinfunction "1_1") (pintype "passive"))
      (node (ref "R901") (pin "P$2") (pinfunction "2_P$2") (pintype "passive"))
    )
    (net (code "46") (name "Net-(IC7B-OUT)") (class "Default")
      (node (ref "C901") (pin "1") (pinfunction "1_1") (pintype "passive"))
      (node (ref "IC7") (pin "7") (pinfunction "OUT_7") (pintype "output"))
      (node (ref "IC8") (pin "3") (pinfunction "+IN_3") (pintype "input"))
      (node (ref "R902") (pin "P$2") (pinfunction "2_P$2") (pintype "passive"))
      (node (ref "R903") (pin "P$2") (pinfunction "2_P$2") (pintype "passive"))
    )
    (net (code "47") (name "Net-(IC8A--IN)") (class "Default")
      (node (ref "C902") (pin "2") (pinfunction "2_2") (pintype "passive"))
      (node (ref "IC8") (pin "2") (pinfunction "-IN_2") (pintype "input"))
      (node (ref "R904") (pin "P$1") (pinfunction "1_P$1") (pintype "passive"))
    )
    (net (code "48") (name "Net-(IC8A-OUT)") (class "Default")
      (node (ref "C902") (pin "1") (pinfunction "1_1") (pintype "passive"))
      (node (ref "IC8") (pin "1") (pinfunction "OUT_1") (pintype "output"))
      (node (ref "IC9") (pin "12") (pinfunction "A0_12") (pintype "bidirectional"))
      (node (ref "R904") (pin "P$2") (pinfunction "2_P$2") (pintype "passive"))
    )
    (net (code "49") (name "Net-(IC8B--IN)") (class "Default")
      (node (ref "IC8") (pin "6") (pinfunction "-IN_6") (pintype "input"))
      (node (ref "IC8") (pin "7") (pinfunction "OUT_7") (pintype "output"))
    )
    (net (code "50") (name "Net-(R305-1)") (class "Default")
      (node (ref "C303") (pin "2") (pinfunction "2_2") (pintype "passive"))
      (node (ref "R305") (pin "P$1") (pinfunction "1_P$1") (pintype "passive"))
    )
    (net (code "51") (name "Net-(R307-1)") (class "Default")
      (node (ref "C304") (pin "2") (pinfunction "2_2") (pintype "passive"))
      (node (ref "R307") (pin "P$1") (pinfunction "1_P$1") (pintype "passive"))
    )
    (net (code "52") (name "Net-(R308-2)") (class "Default")
      (node (ref "C305") (pin "2") (pinfunction "2_2") (pintype "passive"))
      (node (ref "JP401") (pin "1") (pinfunction "1_1") (pintype "passive"))
      (node (ref "R308") (pin "P$2") (pinfunction "2_P$2") (pintype "passive"))
      (node (ref "R309") (pin "P$2") (pinfunction "2_P$2") (pintype "passive"))
    )
    (net (code "53") (name "Net-(R309-1)") (class "Default")
      (node (ref "R309") (pin "P$1") (pinfunction "1_P$1") (pintype "passive"))
      (node (ref "X301") (pin "3") (pinfunction "1_3") (pintype "passive"))
    )
    (net (code "54") (name "Net-(R401-1)") (class "Default")
      (node (ref "JP401") (pin "2") (pinfunction "2_2") (pintype "passive"))
      (node (ref "R401") (pin "P$1") (pinfunction "1_P$1") (pintype "passive"))
      (node (ref "TP401") (pin "1") (pinfunction "KL_1") (pintype "passive"))
    )
    (net (code "55") (name "Net-(R403-1)") (class "Default")
      (node (ref "R403") (pin "P$1") (pinfunction "1_P$1") (pintype "passive"))
      (node (ref "RV401") (pin "1") (pinfunction "S_1") (pintype "passive"))
      (node (ref "RV401") (pin "3") (pinfunction "A_3") (pintype "passive"))
    )
    (net (code "56") (name "Net-(R406-1)") (class "Default")
      (node (ref "C405") (pin "2") (pinfunction "2_2") (pintype "passive"))
      (node (ref "R406") (pin "P$1") (pinfunction "1_P$1") (pintype "passive"))
    )
    (net (code "57") (name "Net-(R408-2)") (class "Default")
      (node (ref "R408") (pin "P$2") (pinfunction "2_P$2") (pintype "passive"))
      (node (ref "RV402") (pin "1") (pinfunction "S_1") (pintype "passive"))
      (node (ref "RV402") (pin "3") (pinfunction "A_3") (pintype "passive"))
    )
    (net (code "58") (name "Net-(R502-1)") (class "Default")
      (node (ref "C501") (pin "2") (pinfunction "2_2") (pintype "passive"))
      (node (ref "R502") (pin "P$1") (pinfunction "1_P$1") (pintype "passive"))
    )
    (net (code "59") (name "Net-(R602-1)") (class "Default")
      (node (ref "C502") (pin "2") (pinfunction "2_2") (pintype "passive"))
      (node (ref "R602") (pin "P$1") (pinfunction "1_P$1") (pintype "passive"))
    )
    (net (code "60") (name "Net-(R701-2)") (class "Default")
      (node (ref "C701") (pin "+") (pinfunction "+_+") (pintype "passive"))
      (node (ref "R701") (pin "P$2") (pinfunction "2_P$2") (pintype "passive"))
      (node (ref "R702") (pin "P$2") (pinfunction "2_P$2") (pintype "passive"))
      (node (ref "R801") (pin "P$1") (pinfunction "1_P$1") (pintype "passive"))
    )
    (net (code "61") (name "Net-(R803-1)") (class "Default")
      (node (ref "R803") (pin "P$1") (pinfunction "1_P$1") (pintype "passive"))
      (node (ref "RV801") (pin "3") (pinfunction "A_3") (pintype "passive"))
    )
    (net (code "62") (name "Net-(R804-2)") (class "Default")
      (node (ref "R804") (pin "P$2") (pinfunction "2_P$2") (pintype "passive"))
      (node (ref "RV801") (pin "2") (pinfunction "E_2") (pintype "passive"))
    )
    (net (code "63") (name "Net-(R805-1)") (class "Default")
      (node (ref "R805") (pin "P$1") (pinfunction "1_P$1") (pintype "passive"))
      (node (ref "RV801") (pin "1") (pinfunction "S_1") (pintype "passive"))
    )
    (net (code "64") (name "Net-(R902-1)") (class "Default")
      (node (ref "JP901") (pin "2") (pinfunction "2_2") (pintype "passive"))
      (node (ref "R902") (pin "P$1") (pinfunction "1_P$1") (pintype "passive"))
    )
    (net (code "65") (name "Net-(R903-1)") (class "Default")
      (node (ref "JP902") (pin "2") (pinfunction "2_2") (pintype "passive"))
      (node (ref "R903") (pin "P$1") (pinfunction "1_P$1") (pintype "passive"))
    )
    (net (code "66") (name "VBAT") (class "Default")
      (node (ref "IC9") (pin "22") (pinfunction "VBAT_22") (pintype "power_in"))
    )
    (net (code "67") (name "unconnected-(IC9-A1-Pad11)") (class "Default")
      (node (ref "IC9") (pin "11") (pinfunction "A1_11") (pintype "bidirectional"))
    )
    (net (code "68") (name "unconnected-(IC9-A2-Pad10)") (class "Default")
      (node (ref "IC9") (pin "10") (pinfunction "A2_10") (pintype "bidirectional"))
    )
    (net (code "69") (name "unconnected-(IC9-A3-Pad9)") (class "Default")
      (node (ref "IC9") (pin "9") (pinfunction "A3_9") (pintype "bidirectional"))
    )
    (net (code "70") (name "unconnected-(IC9-A4-Pad8)") (class "Default")
      (node (ref "IC9") (pin "8") (pinfunction "A4_8") (pintype "bidirectional"))
    )
    (net (code "71") (name "unconnected-(IC9-A5-Pad7)") (class "Default")
      (node (ref "IC9") (pin "7") (pinfunction "A5_7") (pintype "bidirectional"))
    )
    (net (code "72") (name "unconnected-(IC9-D0-Pad13)") (class "Default")
      (node (ref "IC9") (pin "13") (pinfunction "D0_13") (pintype "bidirectional"))
    )
    (net (code "73") (name "unconnected-(IC9-D1-Pad14)") (class "Default")
      (node (ref "IC9") (pin "14") (pinfunction "D1_14") (pintype "bidirectional"))
    )
    (net (code "74") (name "unconnected-(IC9-D2-Pad15)") (class "Default")
      (node (ref "IC9") (pin "15") (pinfunction "D2_15") (pintype "bidirectional"))
    )
    (net (code "75") (name "unconnected-(IC9-D3-Pad16)") (class "Default")
      (node (ref "IC9") (pin "16") (pinfunction "D3_16") (pintype "bidirectional"))
    )
    (net (code "76") (name "unconnected-(IC9-D4-Pad17)") (class "Default")
      (node (ref "IC9") (pin "17") (pinfunction "D4_17") (pintype "bidirectional"))
    )
    (net (code "77") (name "unconnected-(IC9-D5-Pad18)") (class "Default")
      (node (ref "IC9") (pin "18") (pinfunction "D5_18") (pintype "bidirectional"))
    )
    (net (code "78") (name "unconnected-(IC9-D6-Pad19)") (class "Default")
      (node (ref "IC9") (pin "19") (pinfunction "D6_19") (pintype "bidirectional"))
    )
    (net (code "79") (name "unconnected-(IC9-D7-Pad20)") (class "Default")
      (node (ref "IC9") (pin "20") (pinfunction "D7_20") (pintype "bidirectional"))
    )
    (net (code "80") (name "unconnected-(IC9-DAC-Pad6)") (class "Default")
      (node (ref "IC9") (pin "6") (pinfunction "DAC_6") (pintype "bidirectional"))
    )
    (net (code "81") (name "unconnected-(IC9-RX-Pad4)") (class "Default")
      (node (ref "IC9") (pin "4") (pinfunction "RX_4") (pintype "bidirectional"))
    )
    (net (code "82") (name "unconnected-(IC9-TX-Pad3)") (class "Default")
      (node (ref "IC9") (pin "3") (pinfunction "TX_3") (pintype "bidirectional"))
    )
    (net (code "83") (name "unconnected-(IC9-WKP-Pad5)") (class "Default")
      (node (ref "IC9") (pin "5") (pinfunction "WKP_5") (pintype "bidirectional"))
    )
    (net (code "84") (name "unconnected-(IC9-~{RST}-Pad23)") (class "Default")
      (node (ref "IC9") (pin "23") (pinfunction "~{RST}_23") (pintype "bidirectional"))
    )
  )
)
